# Main_STM32F4.net
KiCad netlist of a schematic drawn in Altium Designer
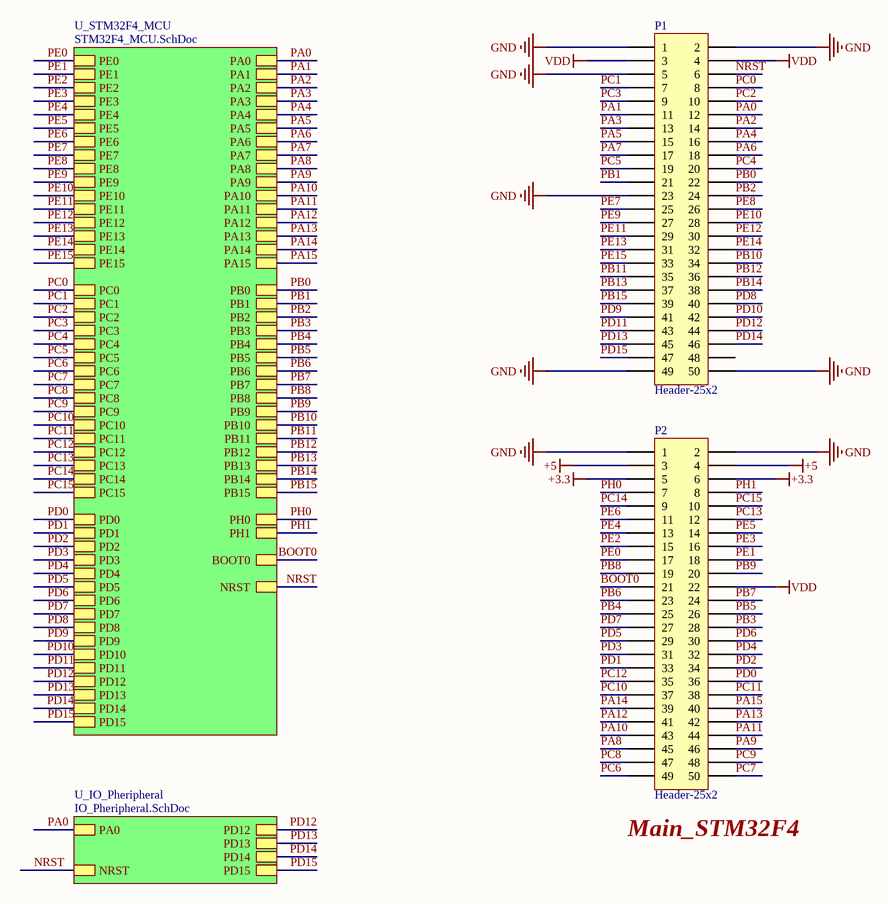
[diagram p0: Main_STM32F4.SchDoc]

(export (version "E")
  (design (tool "Eeschema 10.0.6"))
  (components
    (comp (ref "P1")
      (value "Header-25x2")
      (footprint "Header-25x2")
      (description "Header 8x2 pins")
      (libsource (lib "STM32F4_Board") (part "Header-25x2"))
    )
    (comp (ref "P2")
      (value "Header-25x2")
      (footprint "Header-25x2")
      (description "Header 8x2 pins")
      (libsource (lib "STM32F4_Board") (part "Header-25x2"))
    )
  )
  (nets
    (net (code "1") (name "+3.3") (class "Default")
      (node (ref "P2") (pin "5") (pinfunction "5_5") (pintype "passive"))
      (node (ref "P2") (pin "6") (pinfunction "6_6") (pintype "passive"))
    )
    (net (code "2") (name "+5") (class "Default")
      (node (ref "P2") (pin "3") (pinfunction "3_3") (pintype "passive"))
      (node (ref "P2") (pin "4") (pinfunction "4_4") (pintype "passive"))
    )
    (net (code "3") (name "/BOOT0") (class "Default")
      (node (ref "P2") (pin "21") (pinfunction "21_21") (pintype "passive"))
    )
    (net (code "4") (name "/NRST") (class "Default")
      (node (ref "P1") (pin "6") (pinfunction "6_6") (pintype "passive"))
    )
    (net (code "5") (name "/PA0") (class "Default")
      (node (ref "P1") (pin "12") (pinfunction "12_12") (pintype "passive"))
    )
    (net (code "6") (name "/PA1") (class "Default")
      (node (ref "P1") (pin "11") (pinfunction "11_11") (pintype "passive"))
    )
    (net (code "7") (name "/PA2") (class "Default")
      (node (ref "P1") (pin "14") (pinfunction "14_14") (pintype "passive"))
    )
    (net (code "8") (name "/PA3") (class "Default")
      (node (ref "P1") (pin "13") (pinfunction "13_13") (pintype "passive"))
    )
    (net (code "9") (name "/PA4") (class "Default")
      (node (ref "P1") (pin "16") (pinfunction "16_16") (pintype "passive"))
    )
    (net (code "10") (name "/PA5") (class "Default")
      (node (ref "P1") (pin "15") (pinfunction "15_15") (pintype "passive"))
    )
    (net (code "11") (name "/PA6") (class "Default")
      (node (ref "P1") (pin "18") (pinfunction "18_18") (pintype "passive"))
    )
    (net (code "12") (name "/PA7") (class "Default")
      (node (ref "P1") (pin "17") (pinfunction "17_17") (pintype "passive"))
    )
    (net (code "13") (name "/PA8") (class "Default")
      (node (ref "P2") (pin "45") (pinfunction "45_45") (pintype "passive"))
    )
    (net (code "14") (name "/PA9") (class "Default")
      (node (ref "P2") (pin "46") (pinfunction "46_46") (pintype "passive"))
    )
    (net (code "15") (name "/PA10") (class "Default")
      (node (ref "P2") (pin "43") (pinfunction "43_43") (pintype "passive"))
    )
    (net (code "16") (name "/PA11") (class "Default")
      (node (ref "P2") (pin "44") (pinfunction "44_44") (pintype "passive"))
    )
    (net (code "17") (name "/PA12") (class "Default")
      (node (ref "P2") (pin "41") (pinfunction "41_41") (pintype "passive"))
    )
    (net (code "18") (name "/PA13") (class "Default")
      (node (ref "P2") (pin "42") (pinfunction "42_42") (pintype "passive"))
    )
    (net (code "19") (name "/PA14") (class "Default")
      (node (ref "P2") (pin "39") (pinfunction "39_39") (pintype "passive"))
    )
    (net (code "20") (name "/PA15") (class "Default")
      (node (ref "P2") (pin "40") (pinfunction "40_40") (pintype "passive"))
    )
    (net (code "21") (name "/PB0") (class "Default")
      (node (ref "P1") (pin "22") (pinfunction "22_22") (pintype "passive"))
    )
    (net (code "22") (name "/PB1") (class "Default")
      (node (ref "P1") (pin "21") (pinfunction "21_21") (pintype "passive"))
    )
    (net (code "23") (name "/PB2") (class "Default")
      (node (ref "P1") (pin "24") (pinfunction "24_24") (pintype "passive"))
    )
    (net (code "24") (name "/PB3") (class "Default")
      (node (ref "P2") (pin "28") (pinfunction "28_28") (pintype "passive"))
    )
    (net (code "25") (name "/PB4") (class "Default")
      (node (ref "P2") (pin "25") (pinfunction "25_25") (pintype "passive"))
    )
    (net (code "26") (name "/PB5") (class "Default")
      (node (ref "P2") (pin "26") (pinfunction "26_26") (pintype "passive"))
    )
    (net (code "27") (name "/PB6") (class "Default")
      (node (ref "P2") (pin "23") (pinfunction "23_23") (pintype "passive"))
    )
    (net (code "28") (name "/PB7") (class "Default")
      (node (ref "P2") (pin "24") (pinfunction "24_24") (pintype "passive"))
    )
    (net (code "29") (name "/PB8") (class "Default")
      (node (ref "P2") (pin "19") (pinfunction "19_19") (pintype "passive"))
    )
    (net (code "30") (name "/PB9") (class "Default")
      (node (ref "P2") (pin "20") (pinfunction "20_20") (pintype "passive"))
    )
    (net (code "31") (name "/PB10") (class "Default")
      (node (ref "P1") (pin "34") (pinfunction "34_34") (pintype "passive"))
    )
    (net (code "32") (name "/PB11") (class "Default")
      (node (ref "P1") (pin "35") (pinfunction "35_35") (pintype "passive"))
    )
    (net (code "33") (name "/PB12") (class "Default")
      (node (ref "P1") (pin "36") (pinfunction "36_36") (pintype "passive"))
    )
    (net (code "34") (name "/PB13") (class "Default")
      (node (ref "P1") (pin "37") (pinfunction "37_37") (pintype "passive"))
    )
    (net (code "35") (name "/PB14") (class "Default")
      (node (ref "P1") (pin "38") (pinfunction "38_38") (pintype "passive"))
    )
    (net (code "36") (name "/PB15") (class "Default")
      (node (ref "P1") (pin "39") (pinfunction "39_39") (pintype "passive"))
    )
    (net (code "37") (name "/PC0") (class "Default")
      (node (ref "P1") (pin "8") (pinfunction "8_8") (pintype "passive"))
    )
    (net (code "38") (name "/PC1") (class "Default")
      (node (ref "P1") (pin "7") (pinfunction "7_7") (pintype "passive"))
    )
    (net (code "39") (name "/PC2") (class "Default")
      (node (ref "P1") (pin "10") (pinfunction "10_10") (pintype "passive"))
    )
    (net (code "40") (name "/PC3") (class "Default")
      (node (ref "P1") (pin "9") (pinfunction "9_9") (pintype "passive"))
    )
    (net (code "41") (name "/PC4") (class "Default")
      (node (ref "P1") (pin "20") (pinfunction "20_20") (pintype "passive"))
    )
    (net (code "42") (name "/PC5") (class "Default")
      (node (ref "P1") (pin "19") (pinfunction "19_19") (pintype "passive"))
    )
    (net (code "43") (name "/PC6") (class "Default")
      (node (ref "P2") (pin "49") (pinfunction "49_49") (pintype "passive"))
    )
    (net (code "44") (name "/PC7") (class "Default")
      (node (ref "P2") (pin "50") (pinfunction "50_50") (pintype "passive"))
    )
    (net (code "45") (name "/PC8") (class "Default")
      (node (ref "P2") (pin "47") (pinfunction "47_47") (pintype "passive"))
    )
    (net (code "46") (name "/PC9") (class "Default")
      (node (ref "P2") (pin "48") (pinfunction "48_48") (pintype "passive"))
    )
    (net (code "47") (name "/PC10") (class "Default")
      (node (ref "P2") (pin "37") (pinfunction "37_37") (pintype "passive"))
    )
    (net (code "48") (name "/PC11") (class "Default")
      (node (ref "P2") (pin "38") (pinfunction "38_38") (pintype "passive"))
    )
    (net (code "49") (name "/PC12") (class "Default")
      (node (ref "P2") (pin "35") (pinfunction "35_35") (pintype "passive"))
    )
    (net (code "50") (name "/PC13") (class "Default")
      (node (ref "P2") (pin "12") (pinfunction "12_12") (pintype "passive"))
    )
    (net (code "51") (name "/PC14") (class "Default")
      (node (ref "P2") (pin "9") (pinfunction "9_9") (pintype "passive"))
    )
    (net (code "52") (name "/PC15") (class "Default")
      (node (ref "P2") (pin "10") (pinfunction "10_10") (pintype "passive"))
    )
    (net (code "53") (name "/PD0") (class "Default")
      (node (ref "P2") (pin "36") (pinfunction "36_36") (pintype "passive"))
    )
    (net (code "54") (name "/PD1") (class "Default")
      (node (ref "P2") (pin "33") (pinfunction "33_33") (pintype "passive"))
    )
    (net (code "55") (name "/PD2") (class "Default")
      (node (ref "P2") (pin "34") (pinfunction "34_34") (pintype "passive"))
    )
    (net (code "56") (name "/PD3") (class "Default")
      (node (ref "P2") (pin "31") (pinfunction "31_31") (pintype "passive"))
    )
    (net (code "57") (name "/PD4") (class "Default")
      (node (ref "P2") (pin "32") (pinfunction "32_32") (pintype "passive"))
    )
    (net (code "58") (name "/PD5") (class "Default")
      (node (ref "P2") (pin "29") (pinfunction "29_29") (pintype "passive"))
    )
    (net (code "59") (name "/PD6") (class "Default")
      (node (ref "P2") (pin "30") (pinfunction "30_30") (pintype "passive"))
    )
    (net (code "60") (name "/PD7") (class "Default")
      (node (ref "P2") (pin "27") (pinfunction "27_27") (pintype "passive"))
    )
    (net (code "61") (name "/PD8") (class "Default")
      (node (ref "P1") (pin "40") (pinfunction "40_40") (pintype "passive"))
    )
    (net (code "62") (name "/PD9") (class "Default")
      (node (ref "P1") (pin "41") (pinfunction "41_41") (pintype "passive"))
    )
    (net (code "63") (name "/PD10") (class "Default")
      (node (ref "P1") (pin "42") (pinfunction "42_42") (pintype "passive"))
    )
    (net (code "64") (name "/PD11") (class "Default")
      (node (ref "P1") (pin "43") (pinfunction "43_43") (pintype "passive"))
    )
    (net (code "65") (name "/PD12") (class "Default")
      (node (ref "P1") (pin "44") (pinfunction "44_44") (pintype "passive"))
    )
    (net (code "66") (name "/PD13") (class "Default")
      (node (ref "P1") (pin "45") (pinfunction "45_45") (pintype "passive"))
    )
    (net (code "67") (name "/PD14") (class "Default")
      (node (ref "P1") (pin "46") (pinfunction "46_46") (pintype "passive"))
    )
    (net (code "68") (name "/PD15") (class "Default")
      (node (ref "P1") (pin "47") (pinfunction "47_47") (pintype "passive"))
    )
    (net (code "69") (name "/PE0") (class "Default")
      (node (ref "P2") (pin "17") (pinfunction "17_17") (pintype "passive"))
    )
    (net (code "70") (name "/PE1") (class "Default")
      (node (ref "P2") (pin "18") (pinfunction "18_18") (pintype "passive"))
    )
    (net (code "71") (name "/PE2") (class "Default")
      (node (ref "P2") (pin "15") (pinfunction "15_15") (pintype "passive"))
    )
    (net (code "72") (name "/PE3") (class "Default")
      (node (ref "P2") (pin "16") (pinfunction "16_16") (pintype "passive"))
    )
    (net (code "73") (name "/PE4") (class "Default")
      (node (ref "P2") (pin "13") (pinfunction "13_13") (pintype "passive"))
    )
    (net (code "74") (name "/PE5") (class "Default")
      (node (ref "P2") (pin "14") (pinfunction "14_14") (pintype "passive"))
    )
    (net (code "75") (name "/PE6") (class "Default")
      (node (ref "P2") (pin "11") (pinfunction "11_11") (pintype "passive"))
    )
    (net (code "76") (name "/PE7") (class "Default")
      (node (ref "P1") (pin "25") (pinfunction "25_25") (pintype "passive"))
    )
    (net (code "77") (name "/PE8") (class "Default")
      (node (ref "P1") (pin "26") (pinfunction "26_26") (pintype "passive"))
    )
    (net (code "78") (name "/PE9") (class "Default")
      (node (ref "P1") (pin "27") (pinfunction "27_27") (pintype "passive"))
    )
    (net (code "79") (name "/PE10") (class "Default")
      (node (ref "P1") (pin "28") (pinfunction "28_28") (pintype "passive"))
    )
    (net (code "80") (name "/PE11") (class "Default")
      (node (ref "P1") (pin "29") (pinfunction "29_29") (pintype "passive"))
    )
    (net (code "81") (name "/PE12") (class "Default")
      (node (ref "P1") (pin "30") (pinfunction "30_30") (pintype "passive"))
    )
    (net (code "82") (name "/PE13") (class "Default")
      (node (ref "P1") (pin "31") (pinfunction "31_31") (pintype "passive"))
    )
    (net (code "83") (name "/PE14") (class "Default")
      (node (ref "P1") (pin "32") (pinfunction "32_32") (pintype "passive"))
    )
    (net (code "84") (name "/PE15") (class "Default")
      (node (ref "P1") (pin "33") (pinfunction "33_33") (pintype "passive"))
    )
    (net (code "85") (name "/PH0") (class "Default")
      (node (ref "P2") (pin "7") (pinfunction "7_7") (pintype "passive"))
    )
    (net (code "86") (name "/PH1") (class "Default")
      (node (ref "P2") (pin "8") (pinfunction "8_8") (pintype "passive"))
    )
    (net (code "87") (name "GND") (class "Default")
      (node (ref "P1") (pin "1") (pinfunction "1_1") (pintype "passive"))
      (node (ref "P1") (pin "2") (pinfunction "2_2") (pintype "passive"))
      (node (ref "P1") (pin "23") (pinfunction "23_23") (pintype "passive"))
      (node (ref "P1") (pin "49") (pinfunction "49_49") (pintype "passive"))
      (node (ref "P1") (pin "5") (pinfunction "5_5") (pintype "passive"))
      (node (ref "P1") (pin "50") (pinfunction "50_50") (pintype "passive"))
      (node (ref "P2") (pin "1") (pinfunction "1_1") (pintype "passive"))
      (node (ref "P2") (pin "2") (pinfunction "2_2") (pintype "passive"))
    )
    (net (code "88") (name "VDD") (class "Default")
      (node (ref "P1") (pin "3") (pinfunction "3_3") (pintype "passive"))
      (node (ref "P1") (pin "4") (pinfunction "4_4") (pintype "passive"))
      (node (ref "P2") (pin "22") (pinfunction "22_22") (pintype "passive"))
    )
    (net (code "89") (name "unconnected-(P1-Pad48)") (class "Default")
      (node (ref "P1") (pin "48") (pinfunction "48_48") (pintype "passive"))
    )
  )
)
